# RealCam.net
KiCad netlist of a schematic drawn in EAGLE
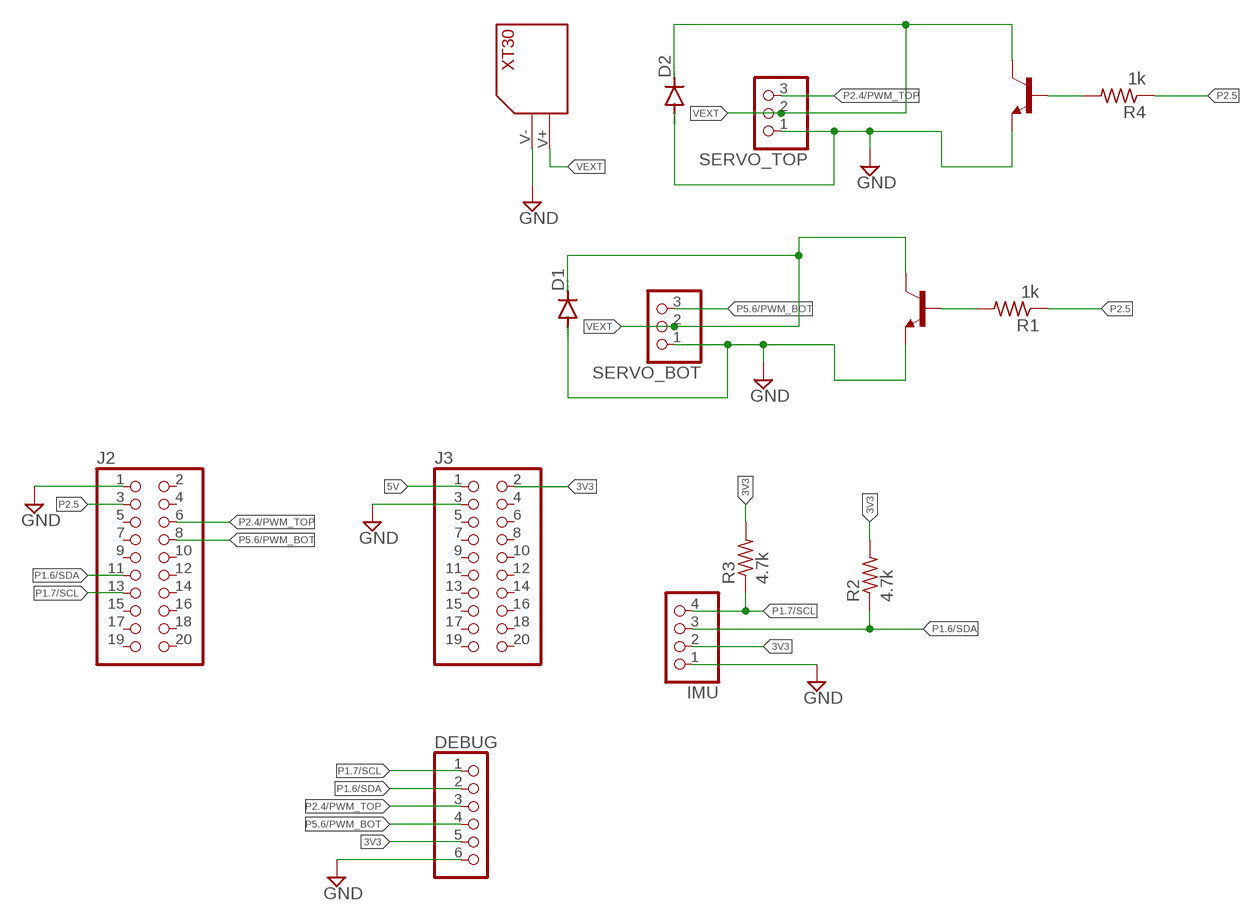
[diagram p0: schematic, sheet 1]

(export (version "E")
  (design (tool "Eeschema 10.0.6"))
  (components
    (comp (ref "D1")
      (value "1N4933")
      (footprint "eagle-import:DO41-10")
      (libsource (lib "eagle-import") (part "1N4933"))
    )
    (comp (ref "D2")
      (value "1N4933")
      (footprint "eagle-import:DO41-10")
      (libsource (lib "eagle-import") (part "1N4933"))
    )
    (comp (ref "DEBUG")
      (value "PINHD-1X6")
      (footprint "eagle-import:1X06")
      (libsource (lib "eagle-import") (part "PINHD-1X6"))
    )
    (comp (ref "IMU")
      (value "PINHD-1X4")
      (footprint "eagle-import:1X04")
      (libsource (lib "eagle-import") (part "PINHD-1X4"))
    )
    (comp (ref "J2")
      (value "PINHD-2X10")
      (footprint "eagle-import:2X10")
      (libsource (lib "eagle-import") (part "PINHD-2X10"))
    )
    (comp (ref "J3")
      (value "PINHD-2X10")
      (footprint "eagle-import:2X10")
      (libsource (lib "eagle-import") (part "PINHD-2X10"))
    )
    (comp (ref "NPN_BC1")
      (value "2N3565")
      (footprint "eagle-import:TO92")
      (libsource (lib "eagle-import") (part "2N3565"))
    )
    (comp (ref "NPN_BC337")
      (value "2N3565")
      (footprint "eagle-import:TO92")
      (libsource (lib "eagle-import") (part "2N3565"))
    )
    (comp (ref "R1")
      (value "1k")
      (footprint "eagle-import:R0805")
      (libsource (lib "eagle-import") (part "R-US_R0805"))
    )
    (comp (ref "R2")
      (value "4.7k")
      (footprint "eagle-import:R0805")
      (libsource (lib "eagle-import") (part "R-US_R0805"))
    )
    (comp (ref "R3")
      (value "4.7k")
      (footprint "eagle-import:R0805")
      (libsource (lib "eagle-import") (part "R-US_R0805"))
    )
    (comp (ref "R4")
      (value "1k")
      (footprint "eagle-import:R0805")
      (libsource (lib "eagle-import") (part "R-US_R0805"))
    )
    (comp (ref "SERVO_BOT")
      (value "PINHD-1X3")
      (footprint "eagle-import:1X03")
      (libsource (lib "eagle-import") (part "PINHD-1X3"))
    )
    (comp (ref "SERVO_TOP")
      (value "PINHD-1X3")
      (footprint "eagle-import:1X03")
      (libsource (lib "eagle-import") (part "PINHD-1X3"))
    )
    (comp (ref "U$1")
      (value "XT30_RIGHT_ANGLE")
      (footprint "eagle-import:XT30_RIGHT_ANGLE")
      (libsource (lib "eagle-import") (part "XT30_RIGHT_ANGLE"))
    )
  )
  (nets
    (net (code "1") (name "3V3") (class "Default")
      (node (ref "DEBUG") (pin "5") (pinfunction "5_5") (pintype "passive"))
      (node (ref "IMU") (pin "2") (pinfunction "2_2") (pintype "passive"))
      (node (ref "J3") (pin "2") (pinfunction "2_2") (pintype "passive"))
      (node (ref "R2") (pin "2") (pinfunction "2_2") (pintype "passive"))
      (node (ref "R3") (pin "2") (pinfunction "2_2") (pintype "passive"))
    )
    (net (code "2") (name "5V") (class "Default")
      (node (ref "J3") (pin "1") (pinfunction "1_1") (pintype "passive"))
    )
    (net (code "3") (name "GND") (class "Default")
      (node (ref "D1") (pin "A") (pinfunction "A_A") (pintype "passive"))
      (node (ref "D2") (pin "A") (pinfunction "A_A") (pintype "passive"))
      (node (ref "DEBUG") (pin "6") (pinfunction "6_6") (pintype "passive"))
      (node (ref "IMU") (pin "1") (pinfunction "1_1") (pintype "passive"))
      (node (ref "J2") (pin "1") (pinfunction "1_1") (pintype "passive"))
      (node (ref "J3") (pin "3") (pinfunction "3_3") (pintype "passive"))
      (node (ref "NPN_BC1") (pin "3") (pinfunction "E_3") (pintype "passive"))
      (node (ref "NPN_BC337") (pin "3") (pinfunction "E_3") (pintype "passive"))
      (node (ref "SERVO_BOT") (pin "1") (pinfunction "1_1") (pintype "passive"))
      (node (ref "SERVO_TOP") (pin "1") (pinfunction "1_1") (pintype "passive"))
      (node (ref "U$1") (pin "V-") (pinfunction "V-_V-") (pintype "bidirectional"))
    )
    (net (code "4") (name "Net-(NPN_BC1-B)") (class "Default")
      (node (ref "NPN_BC1") (pin "2") (pinfunction "B_2") (pintype "passive"))
      (node (ref "R4") (pin "2") (pinfunction "2_2") (pintype "passive"))
    )
    (net (code "5") (name "Net-(NPN_BC337-B)") (class "Default")
      (node (ref "NPN_BC337") (pin "2") (pinfunction "B_2") (pintype "passive"))
      (node (ref "R1") (pin "2") (pinfunction "2_2") (pintype "passive"))
    )
    (net (code "6") (name "P1.6{slash}SDA") (class "Default")
      (node (ref "DEBUG") (pin "2") (pinfunction "2_2") (pintype "passive"))
      (node (ref "IMU") (pin "3") (pinfunction "3_3") (pintype "passive"))
      (node (ref "J2") (pin "11") (pinfunction "11_11") (pintype "passive"))
      (node (ref "R2") (pin "1") (pinfunction "1_1") (pintype "passive"))
    )
    (net (code "7") (name "P1.7{slash}SCL") (class "Default")
      (node (ref "DEBUG") (pin "1") (pinfunction "1_1") (pintype "passive"))
      (node (ref "IMU") (pin "4") (pinfunction "4_4") (pintype "passive"))
      (node (ref "J2") (pin "13") (pinfunction "13_13") (pintype "passive"))
      (node (ref "R3") (pin "1") (pinfunction "1_1") (pintype "passive"))
    )
    (net (code "8") (name "P2.4{slash}PWM_TOP") (class "Default")
      (node (ref "DEBUG") (pin "3") (pinfunction "3_3") (pintype "passive"))
      (node (ref "J2") (pin "6") (pinfunction "6_6") (pintype "passive"))
      (node (ref "SERVO_TOP") (pin "3") (pinfunction "3_3") (pintype "passive"))
    )
    (net (code "9") (name "P2.5") (class "Default")
      (node (ref "J2") (pin "3") (pinfunction "3_3") (pintype "passive"))
      (node (ref "R1") (pin "1") (pinfunction "1_1") (pintype "passive"))
      (node (ref "R4") (pin "1") (pinfunction "1_1") (pintype "passive"))
    )
    (net (code "10") (name "P5.6{slash}PWM_BOT") (class "Default")
      (node (ref "DEBUG") (pin "4") (pinfunction "4_4") (pintype "passive"))
      (node (ref "J2") (pin "8") (pinfunction "8_8") (pintype "passive"))
      (node (ref "SERVO_BOT") (pin "3") (pinfunction "3_3") (pintype "passive"))
    )
    (net (code "11") (name "VEXT") (class "Default")
      (node (ref "D1") (pin "C") (pinfunction "C_C") (pintype "passive"))
      (node (ref "D2") (pin "C") (pinfunction "C_C") (pintype "passive"))
      (node (ref "NPN_BC1") (pin "1") (pinfunction "C_1") (pintype "passive"))
      (node (ref "NPN_BC337") (pin "1") (pinfunction "C_1") (pintype "passive"))
      (node (ref "SERVO_BOT") (pin "2") (pinfunction "2_2") (pintype "passive"))
      (node (ref "SERVO_TOP") (pin "2") (pinfunction "2_2") (pintype "passive"))
      (node (ref "U$1") (pin "V+") (pinfunction "V+_V+") (pintype "bidirectional"))
    )
    (net (code "12") (name "unconnected-(J2-Pad2)") (class "Default")
      (node (ref "J2") (pin "2") (pinfunction "2_2") (pintype "passive"))
    )
    (net (code "13") (name "unconnected-(J2-Pad4)") (class "Default")
      (node (ref "J2") (pin "4") (pinfunction "4_4") (pintype "passive"))
    )
    (net (code "14") (name "unconnected-(J2-Pad5)") (class "Default")
      (node (ref "J2") (pin "5") (pinfunction "5_5") (pintype "passive"))
    )
    (net (code "15") (name "unconnected-(J2-Pad7)") (class "Default")
      (node (ref "J2") (pin "7") (pinfunction "7_7") (pintype "passive"))
    )
    (net (code "16") (name "unconnected-(J2-Pad9)") (class "Default")
      (node (ref "J2") (pin "9") (pinfunction "9_9") (pintype "passive"))
    )
    (net (code "17") (name "unconnected-(J2-Pad10)") (class "Default")
      (node (ref "J2") (pin "10") (pinfunction "10_10") (pintype "passive"))
    )
    (net (code "18") (name "unconnected-(J2-Pad12)") (class "Default")
      (node (ref "J2") (pin "12") (pinfunction "12_12") (pintype "passive"))
    )
    (net (code "19") (name "unconnected-(J2-Pad14)") (class "Default")
      (node (ref "J2") (pin "14") (pinfunction "14_14") (pintype "passive"))
    )
    (net (code "20") (name "unconnected-(J2-Pad15)") (class "Default")
      (node (ref "J2") (pin "15") (pinfunction "15_15") (pintype "passive"))
    )
    (net (code "21") (name "unconnected-(J2-Pad16)") (class "Default")
      (node (ref "J2") (pin "16") (pinfunction "16_16") (pintype "passive"))
    )
    (net (code "22") (name "unconnected-(J2-Pad17)") (class "Default")
      (node (ref "J2") (pin "17") (pinfunction "17_17") (pintype "passive"))
    )
    (net (code "23") (name "unconnected-(J2-Pad18)") (class "Default")
      (node (ref "J2") (pin "18") (pinfunction "18_18") (pintype "passive"))
    )
    (net (code "24") (name "unconnected-(J2-Pad19)") (class "Default")
      (node (ref "J2") (pin "19") (pinfunction "19_19") (pintype "passive"))
    )
    (net (code "25") (name "unconnected-(J2-Pad20)") (class "Default")
      (node (ref "J2") (pin "20") (pinfunction "20_20") (pintype "passive"))
    )
    (net (code "26") (name "unconnected-(J3-Pad4)") (class "Default")
      (node (ref "J3") (pin "4") (pinfunction "4_4") (pintype "passive"))
    )
    (net (code "27") (name "unconnected-(J3-Pad5)") (class "Default")
      (node (ref "J3") (pin "5") (pinfunction "5_5") (pintype "passive"))
    )
    (net (code "28") (name "unconnected-(J3-Pad6)") (class "Default")
      (node (ref "J3") (pin "6") (pinfunction "6_6") (pintype "passive"))
    )
    (net (code "29") (name "unconnected-(J3-Pad7)") (class "Default")
      (node (ref "J3") (pin "7") (pinfunction "7_7") (pintype "passive"))
    )
    (net (code "30") (name "unconnected-(J3-Pad8)") (class "Default")
      (node (ref "J3") (pin "8") (pinfunction "8_8") (pintype "passive"))
    )
    (net (code "31") (name "unconnected-(J3-Pad9)") (class "Default")
      (node (ref "J3") (pin "9") (pinfunction "9_9") (pintype "passive"))
    )
    (net (code "32") (name "unconnected-(J3-Pad10)") (class "Default")
      (node (ref "J3") (pin "10") (pinfunction "10_10") (pintype "passive"))
    )
    (net (code "33") (name "unconnected-(J3-Pad11)") (class "Default")
      (node (ref "J3") (pin "11") (pinfunction "11_11") (pintype "passive"))
    )
    (net (code "34") (name "unconnected-(J3-Pad12)") (class "Default")
      (node (ref "J3") (pin "12") (pinfunction "12_12") (pintype "passive"))
    )
    (net (code "35") (name "unconnected-(J3-Pad13)") (class "Default")
      (node (ref "J3") (pin "13") (pinfunction "13_13") (pintype "passive"))
    )
    (net (code "36") (name "unconnected-(J3-Pad14)") (class "Default")
      (node (ref "J3") (pin "14") (pinfunction "14_14") (pintype "passive"))
    )
    (net (code "37") (name "unconnected-(J3-Pad15)") (class "Default")
      (node (ref "J3") (pin "15") (pinfunction "15_15") (pintype "passive"))
    )
    (net (code "38") (name "unconnected-(J3-Pad16)") (class "Default")
      (node (ref "J3") (pin "16") (pinfunction "16_16") (pintype "passive"))
    )
    (net (code "39") (name "unconnected-(J3-Pad17)") (class "Default")
      (node (ref "J3") (pin "17") (pinfunction "17_17") (pintype "passive"))
    )
    (net (code "40") (name "unconnected-(J3-Pad18)") (class "Default")
      (node (ref "J3") (pin "18") (pinfunction "18_18") (pintype "passive"))
    )
    (net (code "41") (name "unconnected-(J3-Pad19)") (class "Default")
      (node (ref "J3") (pin "19") (pinfunction "19_19") (pintype "passive"))
    )
    (net (code "42") (name "unconnected-(J3-Pad20)") (class "Default")
      (node (ref "J3") (pin "20") (pinfunction "20_20") (pintype "passive"))
    )
  )
)
